# GyroSense.net
KiCad netlist of a schematic drawn in Altium Designer
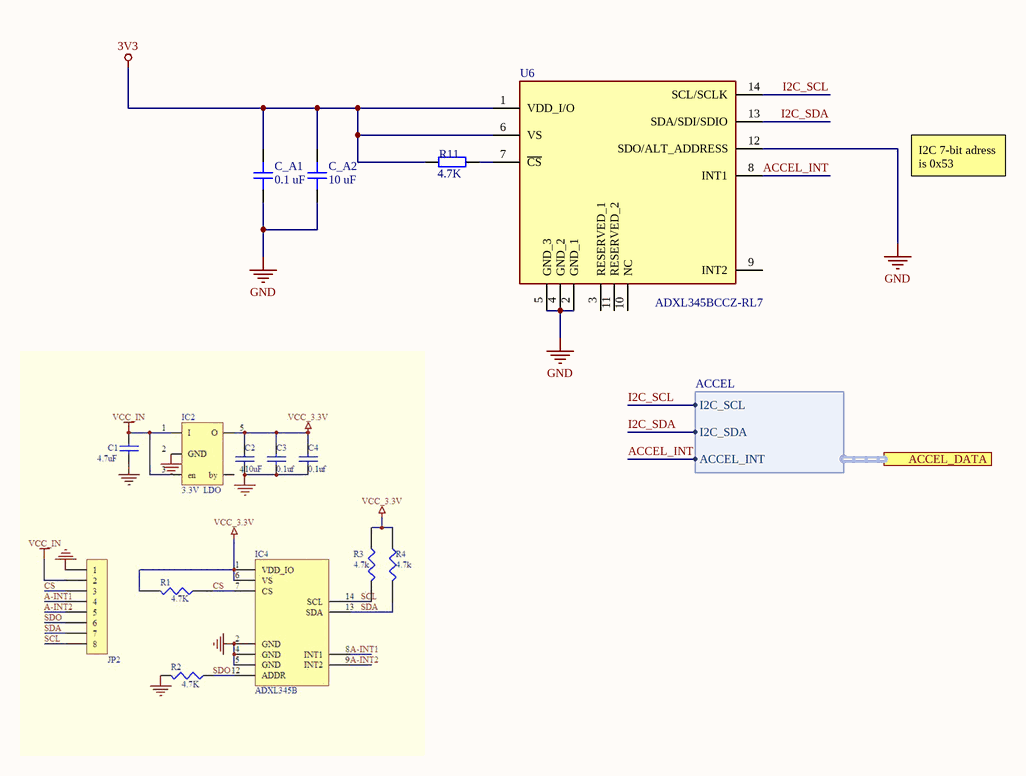
[diagram p0: GyroSense.SchDoc]

(export (version "E")
  (design (tool "Eeschema 10.0.6"))
  (components
    (comp (ref "C_A1")
      (value "0.1 uF")
      (footprint "CAP_0603")
      (description "Capacitor SMD 0603")
      (libsource (lib "Generic library") (part "CAP_0603"))
    )
    (comp (ref "C_A2")
      (value "10 uF")
      (footprint "CAP_0603")
      (description "Capacitor SMD 0603")
      (libsource (lib "Generic library") (part "CAP_0603"))
    )
    (comp (ref "R11")
      (value "4.7K")
      (footprint "RES_0603")
      (description "Resistor SMD 0603")
      (libsource (lib "Generic library") (part "RES_0603"))
    )
    (comp (ref "U6")
      (value "ADXL345BCCZ-RL7")
      (footprint "ADXL345BCCZRL7")
      (fields (field (name "MOUSER PART NUMBER") "584-ADXL345BCCZ-R7"))
      (libsource (lib "Schlib1") (part "ADXL345BCCZ-RL7"))
    )
  )
  (nets
    (net (code "2") (name "/ACCEL_INT") (class "Default")
      (node (ref "U6") (pin "8") (pinfunction "INT1_8") (pintype "passive"))
    )
    (net (code "3") (name "/I2C_SCL") (class "Default")
      (node (ref "U6") (pin "14") (pinfunction "SCL/SCLK_14") (pintype "passive"))
    )
    (net (code "4") (name "/I2C_SDA") (class "Default")
      (node (ref "U6") (pin "13") (pinfunction "SDA/SDI/SDIO_13") (pintype "passive"))
    )
    (net (code "6") (name "3V3") (class "Default")
      (node (ref "C_A1") (pin "2") (pinfunction "2_2") (pintype "passive"))
      (node (ref "C_A2") (pin "2") (pinfunction "2_2") (pintype "passive"))
      (node (ref "R11") (pin "1") (pinfunction "1_1") (pintype "passive"))
      (node (ref "U6") (pin "1") (pinfunction "VDD_I/O_1") (pintype "passive"))
      (node (ref "U6") (pin "6") (pinfunction "VS_6") (pintype "passive"))
    )
    (net (code "7") (name "GND") (class "Default")
      (node (ref "C_A1") (pin "1") (pinfunction "1_1") (pintype "passive"))
      (node (ref "C_A2") (pin "1") (pinfunction "1_1") (pintype "passive"))
      (node (ref "U6") (pin "12") (pinfunction "SDO/ALT_ADDRESS_12") (pintype "passive"))
      (node (ref "U6") (pin "2") (pinfunction "GND_1_2") (pintype "passive"))
      (node (ref "U6") (pin "4") (pinfunction "GND_2_4") (pintype "passive"))
      (node (ref "U6") (pin "5") (pinfunction "GND_3_5") (pintype "passive"))
    )
    (net (code "8") (name "Net-(U6-~{CS})") (class "Default")
      (node (ref "R11") (pin "2") (pinfunction "2_2") (pintype "passive"))
      (node (ref "U6") (pin "7") (pinfunction "~{CS}_7") (pintype "passive"))
    )
    (net (code "9") (name "unconnected-(U6-INT2-Pad9)") (class "Default")
      (node (ref "U6") (pin "9") (pinfunction "INT2_9") (pintype "passive"))
    )
    (net (code "10") (name "unconnected-(U6-NC-Pad10)") (class "Default")
      (node (ref "U6") (pin "10") (pinfunction "NC_10") (pintype "passive"))
    )
    (net (code "11") (name "unconnected-(U6-RESERVED_1-Pad3)") (class "Default")
      (node (ref "U6") (pin "3") (pinfunction "RESERVED_1_3") (pintype "passive"))
    )
    (net (code "12") (name "unconnected-(U6-RESERVED_2-Pad11)") (class "Default")
      (node (ref "U6") (pin "11") (pinfunction "RESERVED_2_11") (pintype "passive"))
    )
  )
)
